# 3_7.net
KiCad netlist of a schematic drawn in Altium Designer
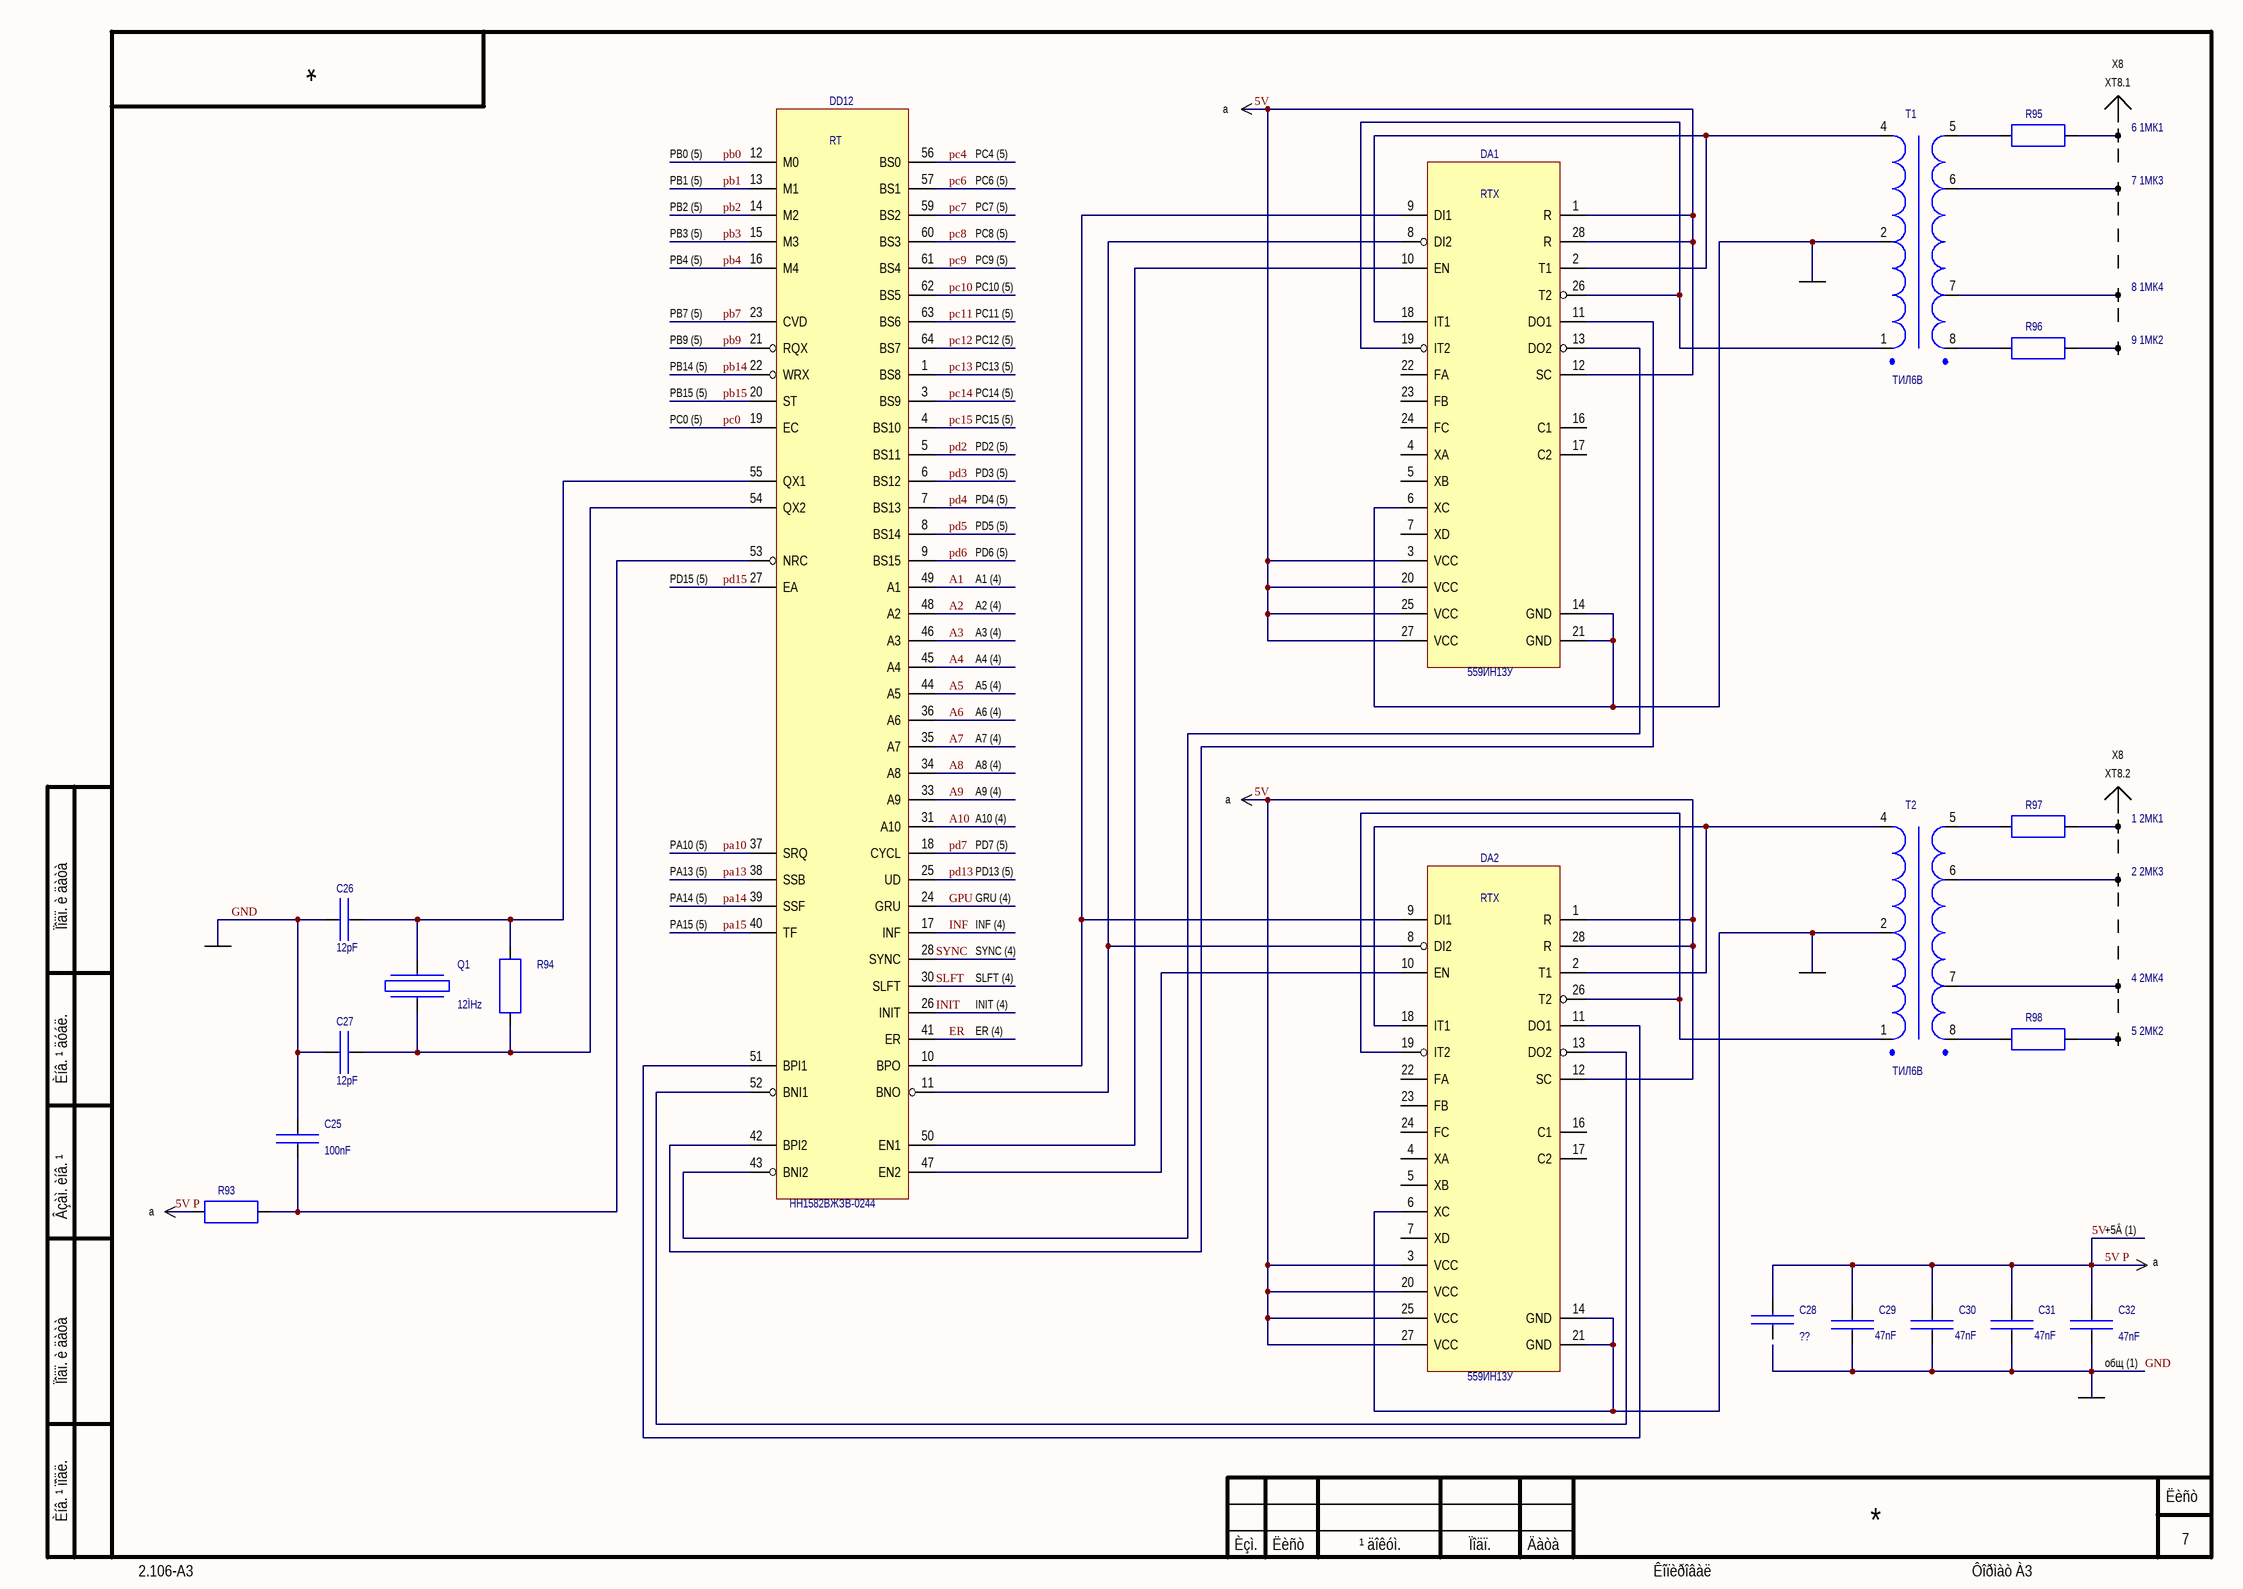
[diagram p0: Э3_7.SchDoc]

(export (version "E")
  (design (tool "Eeschema 10.0.6"))
  (components
    (comp (ref "C25") (value "100nF") (footprint "PcbLib1:CAP0805") (libsource (lib "Schlib1") (part "C_2")))
    (comp (ref "C26") (value "12pF") (footprint "PcbLib1:CAP0805") (libsource (lib "Schlib1") (part "C")))
    (comp (ref "C27") (value "12pF") (footprint "PcbLib1:CAP0805") (libsource (lib "Schlib1") (part "C")))
    (comp (ref "C28") (value "??") (footprint "PcbLib1:CAP0805") (libsource (lib "Schlib1") (part "C")))
    (comp (ref "C29") (value "47nF") (footprint "PcbLib1:CAP0805") (libsource (lib "Schlib1") (part "C")))
    (comp (ref "C30") (value "47nF") (footprint "PcbLib1:CAP0805") (libsource (lib "Schlib1") (part "C")))
    (comp (ref "C31") (value "47nF") (footprint "PcbLib1:CAP0805") (libsource (lib "Schlib1") (part "C")))
    (comp (ref "C32") (value "47nF") (footprint "PcbLib1:CAP0805") (libsource (lib "Schlib1") (part "C_2")))
    (comp (ref "DA1")
      (value "559ИН13У")
      (footprint "PcbLib1:H09.28-1B")
      (libsource (lib "Schlib1") (part "559ИН13У"))
    )
    (comp (ref "DA2")
      (value "559ИН13У")
      (footprint "PcbLib1:H09.28-1B")
      (libsource (lib "Schlib1") (part "559ИН13У"))
    )
    (comp (ref "DD12")
      (value "НН1582ВЖЗВ-0244")
      (footprint "PcbLib1:H18.64-1B")
      (libsource (lib "Schlib1") (part "НН1582ВЖЗВ-0244"))
    )
    (comp (ref "Q1") (value "12МHz") (libsource (lib "Schlib1") (part "Q_1")))
    (comp (ref "R93") (value "100k") (footprint "PcbLib1:RES0805") (libsource (lib "Schlib1") (part "R")))
    (comp (ref "R94") (value "240k") (footprint "PcbLib1:RES0805") (libsource (lib "Schlib1") (part "R")))
    (comp (ref "R95") (value "56") (footprint "PcbLib1:RES0805") (libsource (lib "Schlib1") (part "R")))
    (comp (ref "R96") (value "56") (footprint "PcbLib1:RES0805") (libsource (lib "Schlib1") (part "R_1")))
    (comp (ref "R97") (value "56") (footprint "PcbLib1:RES0805") (libsource (lib "Schlib1") (part "R")))
    (comp (ref "R98") (value "56") (footprint "PcbLib1:RES0805") (libsource (lib "Schlib1") (part "R")))
    (comp (ref "T1") (value "ТИЛ6B") (footprint "PcbLib1:TIL6V") (libsource (lib "Schlib1") (part "ТИЛ6B")))
    (comp (ref "T2") (value "ТИЛ6B") (footprint "PcbLib1:TIL6V") (libsource (lib "Schlib1") (part "ТИЛ6B")))
    (comp (ref "X8") (value "1 2МК1") (footprint "PcbLib1:PLD10") (libsource (lib "Schlib1") (part "PLD10")))
  )
  (nets
    (net (code "1") (name "/5V") (class "Default")
      (node (ref "C28") (pin "1") (pintype "passive"))
      (node (ref "C29") (pin "2") (pintype "passive"))
      (node (ref "C30") (pin "2") (pintype "passive"))
      (node (ref "C31") (pin "2") (pintype "passive"))
      (node (ref "C32") (pin "2") (pintype "passive"))
      (node (ref "DA1") (pin "1") (pinfunction "R_1") (pintype "passive"))
      (node (ref "DA1") (pin "12") (pinfunction "SC_12") (pintype "passive"))
      (node (ref "DA1") (pin "20") (pinfunction "VCC_20") (pintype "passive"))
      (node (ref "DA1") (pin "25") (pinfunction "VCC_25") (pintype "passive"))
      (node (ref "DA1") (pin "27") (pinfunction "VCC_27") (pintype "passive"))
      (node (ref "DA1") (pin "28") (pinfunction "R_28") (pintype "passive"))
      (node (ref "DA1") (pin "3") (pinfunction "VCC_3") (pintype "passive"))
      (node (ref "DA2") (pin "1") (pinfunction "R_1") (pintype "passive"))
      (node (ref "DA2") (pin "12") (pinfunction "SC_12") (pintype "passive"))
      (node (ref "DA2") (pin "20") (pinfunction "VCC_20") (pintype "passive"))
      (node (ref "DA2") (pin "25") (pinfunction "VCC_25") (pintype "passive"))
      (node (ref "DA2") (pin "27") (pinfunction "VCC_27") (pintype "passive"))
      (node (ref "DA2") (pin "28") (pinfunction "R_28") (pintype "passive"))
      (node (ref "DA2") (pin "3") (pinfunction "VCC_3") (pintype "passive"))
      (node (ref "R93") (pin "1") (pintype "passive"))
    )
    (net (code "2") (name "/A1") (class "Default")
      (node (ref "DD12") (pin "49") (pinfunction "A1_49") (pintype "passive"))
    )
    (net (code "3") (name "/A2") (class "Default")
      (node (ref "DD12") (pin "48") (pinfunction "A2_48") (pintype "passive"))
    )
    (net (code "4") (name "/A3") (class "Default")
      (node (ref "DD12") (pin "46") (pinfunction "A3_46") (pintype "passive"))
    )
    (net (code "5") (name "/A4") (class "Default")
      (node (ref "DD12") (pin "45") (pinfunction "A4_45") (pintype "passive"))
    )
    (net (code "6") (name "/A5") (class "Default")
      (node (ref "DD12") (pin "44") (pinfunction "A5_44") (pintype "passive"))
    )
    (net (code "7") (name "/A6") (class "Default")
      (node (ref "DD12") (pin "36") (pinfunction "A6_36") (pintype "passive"))
    )
    (net (code "8") (name "/A7") (class "Default")
      (node (ref "DD12") (pin "35") (pinfunction "A7_35") (pintype "passive"))
    )
    (net (code "9") (name "/A8") (class "Default")
      (node (ref "DD12") (pin "34") (pinfunction "A8_34") (pintype "passive"))
    )
    (net (code "10") (name "/A9") (class "Default")
      (node (ref "DD12") (pin "33") (pinfunction "A9_33") (pintype "passive"))
    )
    (net (code "11") (name "/A10") (class "Default")
      (node (ref "DD12") (pin "31") (pinfunction "A10_31") (pintype "passive"))
    )
    (net (code "12") (name "/ER") (class "Default")
      (node (ref "DD12") (pin "41") (pinfunction "ER_41") (pintype "passive"))
    )
    (net (code "13") (name "/GND") (class "Default")
      (node (ref "C25") (pin "2") (pintype "passive"))
      (node (ref "C26") (pin "1") (pintype "passive"))
      (node (ref "C27") (pin "1") (pintype "passive"))
      (node (ref "C29") (pin "1") (pintype "passive"))
      (node (ref "C30") (pin "1") (pintype "passive"))
      (node (ref "C31") (pin "1") (pintype "passive"))
      (node (ref "C32") (pin "1") (pintype "passive"))
      (node (ref "DA2") (pin "14") (pinfunction "GND_14") (pintype "passive"))
      (node (ref "DA2") (pin "21") (pinfunction "GND_21") (pintype "passive"))
      (node (ref "DA2") (pin "6") (pinfunction "XC_6") (pintype "passive"))
      (node (ref "T2") (pin "2") (pintype "passive"))
    )
    (net (code "14") (name "/GPU") (class "Default")
      (node (ref "DD12") (pin "24") (pinfunction "GRU_24") (pintype "passive"))
    )
    (net (code "15") (name "/INF") (class "Default")
      (node (ref "DD12") (pin "17") (pinfunction "INF_17") (pintype "passive"))
    )
    (net (code "16") (name "/INIT") (class "Default")
      (node (ref "DD12") (pin "26") (pinfunction "INIT_26") (pintype "passive"))
    )
    (net (code "17") (name "/SLFT") (class "Default")
      (node (ref "DD12") (pin "30") (pinfunction "SLFT_30") (pintype "passive"))
    )
    (net (code "18") (name "/SYNC") (class "Default")
      (node (ref "DD12") (pin "28") (pinfunction "SYNC_28") (pintype "passive"))
    )
    (net (code "19") (name "/pa10") (class "Default")
      (node (ref "DD12") (pin "37") (pinfunction "SRQ_37") (pintype "passive"))
    )
    (net (code "20") (name "/pa13") (class "Default")
      (node (ref "DD12") (pin "38") (pinfunction "SSB_38") (pintype "passive"))
    )
    (net (code "21") (name "/pa14") (class "Default")
      (node (ref "DD12") (pin "39") (pinfunction "SSF_39") (pintype "passive"))
    )
    (net (code "22") (name "/pa15") (class "Default")
      (node (ref "DD12") (pin "40") (pinfunction "TF_40") (pintype "passive"))
    )
    (net (code "23") (name "/pb0") (class "Default")
      (node (ref "DD12") (pin "12") (pinfunction "M0_12") (pintype "passive"))
    )
    (net (code "24") (name "/pb1") (class "Default")
      (node (ref "DD12") (pin "13") (pinfunction "M1_13") (pintype "passive"))
    )
    (net (code "25") (name "/pb2") (class "Default")
      (node (ref "DD12") (pin "14") (pinfunction "M2_14") (pintype "passive"))
    )
    (net (code "26") (name "/pb3") (class "Default")
      (node (ref "DD12") (pin "15") (pinfunction "M3_15") (pintype "passive"))
    )
    (net (code "27") (name "/pb4") (class "Default")
      (node (ref "DD12") (pin "16") (pinfunction "M4_16") (pintype "passive"))
    )
    (net (code "28") (name "/pb7") (class "Default")
      (node (ref "DD12") (pin "23") (pinfunction "CVD_23") (pintype "passive"))
    )
    (net (code "29") (name "/pb9") (class "Default")
      (node (ref "DD12") (pin "21") (pinfunction "RQX_21") (pintype "passive"))
    )
    (net (code "30") (name "/pb14") (class "Default")
      (node (ref "DD12") (pin "22") (pinfunction "WRX_22") (pintype "passive"))
    )
    (net (code "31") (name "/pb15") (class "Default")
      (node (ref "DD12") (pin "20") (pinfunction "ST_20") (pintype "passive"))
    )
    (net (code "32") (name "/pc0") (class "Default")
      (node (ref "DD12") (pin "19") (pinfunction "EC_19") (pintype "passive"))
    )
    (net (code "33") (name "/pc4") (class "Default")
      (node (ref "DD12") (pin "56") (pinfunction "BS0_56") (pintype "passive"))
    )
    (net (code "34") (name "/pc6") (class "Default")
      (node (ref "DD12") (pin "57") (pinfunction "BS1_57") (pintype "passive"))
    )
    (net (code "35") (name "/pc7") (class "Default")
      (node (ref "DD12") (pin "59") (pinfunction "BS2_59") (pintype "passive"))
    )
    (net (code "36") (name "/pc8") (class "Default")
      (node (ref "DD12") (pin "60") (pinfunction "BS3_60") (pintype "passive"))
    )
    (net (code "37") (name "/pc9") (class "Default")
      (node (ref "DD12") (pin "61") (pinfunction "BS4_61") (pintype "passive"))
    )
    (net (code "38") (name "/pc10") (class "Default")
      (node (ref "DD12") (pin "62") (pinfunction "BS5_62") (pintype "passive"))
    )
    (net (code "39") (name "/pc11") (class "Default")
      (node (ref "DD12") (pin "63") (pinfunction "BS6_63") (pintype "passive"))
    )
    (net (code "40") (name "/pc12") (class "Default")
      (node (ref "DD12") (pin "64") (pinfunction "BS7_64") (pintype "passive"))
    )
    (net (code "41") (name "/pc13") (class "Default")
      (node (ref "DD12") (pin "1") (pinfunction "BS8_1") (pintype "passive"))
    )
    (net (code "42") (name "/pc14") (class "Default")
      (node (ref "DD12") (pin "3") (pinfunction "BS9_3") (pintype "passive"))
    )
    (net (code "43") (name "/pc15") (class "Default")
      (node (ref "DD12") (pin "4") (pinfunction "BS10_4") (pintype "passive"))
    )
    (net (code "44") (name "/pd2") (class "Default")
      (node (ref "DD12") (pin "5") (pinfunction "BS11_5") (pintype "passive"))
    )
    (net (code "45") (name "/pd3") (class "Default")
      (node (ref "DD12") (pin "6") (pinfunction "BS12_6") (pintype "passive"))
    )
    (net (code "46") (name "/pd4") (class "Default")
      (node (ref "DD12") (pin "7") (pinfunction "BS13_7") (pintype "passive"))
    )
    (net (code "47") (name "/pd5") (class "Default")
      (node (ref "DD12") (pin "8") (pinfunction "BS14_8") (pintype "passive"))
    )
    (net (code "48") (name "/pd6") (class "Default")
      (node (ref "DD12") (pin "9") (pinfunction "BS15_9") (pintype "passive"))
    )
    (net (code "49") (name "/pd7") (class "Default")
      (node (ref "DD12") (pin "18") (pinfunction "CYCL_18") (pintype "passive"))
    )
    (net (code "50") (name "/pd13") (class "Default")
      (node (ref "DD12") (pin "25") (pinfunction "UD_25") (pintype "passive"))
    )
    (net (code "51") (name "/pd15") (class "Default")
      (node (ref "DD12") (pin "27") (pinfunction "EA_27") (pintype "passive"))
    )
    (net (code "52") (name "Net-(DA1-DI1)") (class "Default")
      (node (ref "DA1") (pin "9") (pinfunction "DI1_9") (pintype "passive"))
      (node (ref "DA2") (pin "9") (pinfunction "DI1_9") (pintype "passive"))
      (node (ref "DD12") (pin "10") (pinfunction "BPO_10") (pintype "passive"))
    )
    (net (code "53") (name "Net-(DA1-DI2)") (class "Default")
      (node (ref "DA1") (pin "8") (pinfunction "DI2_8") (pintype "passive"))
      (node (ref "DA2") (pin "8") (pinfunction "DI2_8") (pintype "passive"))
      (node (ref "DD12") (pin "11") (pinfunction "BNO_11") (pintype "passive"))
    )
    (net (code "54") (name "Net-(DA1-DO1)") (class "Default")
      (node (ref "DA1") (pin "11") (pinfunction "DO1_11") (pintype "passive"))
      (node (ref "DD12") (pin "42") (pinfunction "BPI2_42") (pintype "passive"))
    )
    (net (code "55") (name "Net-(DA1-DO2)") (class "Default")
      (node (ref "DA1") (pin "13") (pinfunction "DO2_13") (pintype "passive"))
      (node (ref "DD12") (pin "43") (pinfunction "BNI2_43") (pintype "passive"))
    )
    (net (code "56") (name "Net-(DA1-EN)") (class "Default")
      (node (ref "DA1") (pin "10") (pinfunction "EN_10") (pintype "passive"))
      (node (ref "DD12") (pin "50") (pinfunction "EN1_50") (pintype "passive"))
    )
    (net (code "57") (name "Net-(DA1-IT1)") (class "Default")
      (node (ref "DA1") (pin "18") (pinfunction "IT1_18") (pintype "passive"))
      (node (ref "DA1") (pin "2") (pinfunction "T1_2") (pintype "passive"))
      (node (ref "T1") (pin "4") (pintype "passive"))
    )
    (net (code "58") (name "Net-(DA1-IT2)") (class "Default")
      (node (ref "DA1") (pin "19") (pinfunction "IT2_19") (pintype "passive"))
      (node (ref "DA1") (pin "26") (pinfunction "T2_26") (pintype "passive"))
      (node (ref "T1") (pin "1") (pintype "passive"))
    )
    (net (code "59") (name "Net-(DA1-XC)") (class "Default")
      (node (ref "DA1") (pin "14") (pinfunction "GND_14") (pintype "passive"))
      (node (ref "DA1") (pin "21") (pinfunction "GND_21") (pintype "passive"))
      (node (ref "DA1") (pin "6") (pinfunction "XC_6") (pintype "passive"))
      (node (ref "T1") (pin "2") (pintype "passive"))
    )
    (net (code "60") (name "Net-(DA2-DO1)") (class "Default")
      (node (ref "DA2") (pin "11") (pinfunction "DO1_11") (pintype "passive"))
      (node (ref "DD12") (pin "51") (pinfunction "BPI1_51") (pintype "passive"))
    )
    (net (code "61") (name "Net-(DA2-DO2)") (class "Default")
      (node (ref "DA2") (pin "13") (pinfunction "DO2_13") (pintype "passive"))
      (node (ref "DD12") (pin "52") (pinfunction "BNI1_52") (pintype "passive"))
    )
    (net (code "62") (name "Net-(DA2-EN)") (class "Default")
      (node (ref "DA2") (pin "10") (pinfunction "EN_10") (pintype "passive"))
      (node (ref "DD12") (pin "47") (pinfunction "EN2_47") (pintype "passive"))
    )
    (net (code "63") (name "Net-(DA2-IT1)") (class "Default")
      (node (ref "DA2") (pin "18") (pinfunction "IT1_18") (pintype "passive"))
      (node (ref "DA2") (pin "2") (pinfunction "T1_2") (pintype "passive"))
      (node (ref "T2") (pin "4") (pintype "passive"))
    )
    (net (code "64") (name "Net-(DA2-IT2)") (class "Default")
      (node (ref "DA2") (pin "19") (pinfunction "IT2_19") (pintype "passive"))
      (node (ref "DA2") (pin "26") (pinfunction "T2_26") (pintype "passive"))
      (node (ref "T2") (pin "1") (pintype "passive"))
    )
    (net (code "65") (name "Net-(DD12-NRC)") (class "Default")
      (node (ref "C25") (pin "1") (pintype "passive"))
      (node (ref "DD12") (pin "53") (pinfunction "NRC_53") (pintype "passive"))
      (node (ref "R93") (pin "2") (pintype "passive"))
    )
    (net (code "66") (name "Net-(DD12-QX1)") (class "Default")
      (node (ref "C26") (pin "2") (pintype "passive"))
      (node (ref "DD12") (pin "55") (pinfunction "QX1_55") (pintype "passive"))
      (node (ref "Q1") (pin "2") (pintype "passive"))
      (node (ref "R94") (pin "2") (pintype "passive"))
    )
    (net (code "67") (name "Net-(DD12-QX2)") (class "Default")
      (node (ref "C27") (pin "2") (pintype "passive"))
      (node (ref "DD12") (pin "54") (pinfunction "QX2_54") (pintype "passive"))
      (node (ref "Q1") (pin "1") (pintype "passive"))
      (node (ref "R94") (pin "1") (pintype "passive"))
    )
    (net (code "68") (name "Net-(R95-Pad1)") (class "Default")
      (node (ref "R95") (pin "1") (pintype "passive"))
      (node (ref "T1") (pin "5") (pintype "passive"))
    )
    (net (code "69") (name "Net-(R96-Pad1)") (class "Default")
      (node (ref "R96") (pin "1") (pintype "passive"))
      (node (ref "T1") (pin "8") (pintype "passive"))
    )
    (net (code "70") (name "Net-(R97-Pad1)") (class "Default")
      (node (ref "R97") (pin "1") (pintype "passive"))
      (node (ref "T2") (pin "5") (pintype "passive"))
    )
    (net (code "71") (name "Net-(R97-Pad2)") (class "Default")
      (node (ref "R97") (pin "2") (pintype "passive"))
      (node (ref "X8") (pin "1") (pinfunction "1_1") (pintype "passive"))
    )
    (net (code "72") (name "Net-(R98-Pad1)") (class "Default")
      (node (ref "R98") (pin "1") (pintype "passive"))
      (node (ref "T2") (pin "8") (pintype "passive"))
    )
    (net (code "73") (name "Net-(X8B-1)") (class "Default")
      (node (ref "T2") (pin "6") (pintype "passive"))
      (node (ref "X8") (pin "2") (pinfunction "1_2") (pintype "passive"))
    )
    (net (code "74") (name "Net-(X8D-1)") (class "Default")
      (node (ref "T2") (pin "7") (pintype "passive"))
      (node (ref "X8") (pin "4") (pinfunction "1_4") (pintype "passive"))
    )
    (net (code "75") (name "Net-(X8E-1)") (class "Default")
      (node (ref "R98") (pin "2") (pintype "passive"))
      (node (ref "X8") (pin "5") (pinfunction "1_5") (pintype "passive"))
    )
    (net (code "76") (name "Net-(X8F-1)") (class "Default")
      (node (ref "R95") (pin "2") (pintype "passive"))
      (node (ref "X8") (pin "6") (pinfunction "1_6") (pintype "passive"))
    )
    (net (code "77") (name "Net-(X8G-1)") (class "Default")
      (node (ref "T1") (pin "6") (pintype "passive"))
      (node (ref "X8") (pin "7") (pinfunction "1_7") (pintype "passive"))
    )
    (net (code "78") (name "Net-(X8H-1)") (class "Default")
      (node (ref "T1") (pin "7") (pintype "passive"))
      (node (ref "X8") (pin "8") (pinfunction "1_8") (pintype "passive"))
    )
    (net (code "79") (name "Net-(X8I-1)") (class "Default")
      (node (ref "R96") (pin "2") (pintype "passive"))
      (node (ref "X8") (pin "9") (pinfunction "1_9") (pintype "passive"))
    )
    (net (code "80") (name "unconnected-(C28-Pad2)") (class "Default")
      (node (ref "C28") (pin "2") (pintype "passive"))
    )
    (net (code "81") (name "unconnected-(DA1-C1-Pad16)") (class "Default")
      (node (ref "DA1") (pin "16") (pinfunction "C1_16") (pintype "passive"))
    )
    (net (code "82") (name "unconnected-(DA1-C2-Pad17)") (class "Default")
      (node (ref "DA1") (pin "17") (pinfunction "C2_17") (pintype "passive"))
    )
    (net (code "83") (name "unconnected-(DA1-FA-Pad22)") (class "Default")
      (node (ref "DA1") (pin "22") (pinfunction "FA_22") (pintype "passive"))
    )
    (net (code "84") (name "unconnected-(DA1-FB-Pad23)") (class "Default")
      (node (ref "DA1") (pin "23") (pinfunction "FB_23") (pintype "passive"))
    )
    (net (code "85") (name "unconnected-(DA1-FC-Pad24)") (class "Default")
      (node (ref "DA1") (pin "24") (pinfunction "FC_24") (pintype "passive"))
    )
    (net (code "86") (name "unconnected-(DA1-XA-Pad4)") (class "Default")
      (node (ref "DA1") (pin "4") (pinfunction "XA_4") (pintype "passive"))
    )
    (net (code "87") (name "unconnected-(DA1-XB-Pad5)") (class "Default")
      (node (ref "DA1") (pin "5") (pinfunction "XB_5") (pintype "passive"))
    )
    (net (code "88") (name "unconnected-(DA1-XD-Pad7)") (class "Default")
      (node (ref "DA1") (pin "7") (pinfunction "XD_7") (pintype "passive"))
    )
    (net (code "89") (name "unconnected-(DA2-C1-Pad16)") (class "Default")
      (node (ref "DA2") (pin "16") (pinfunction "C1_16") (pintype "passive"))
    )
    (net (code "90") (name "unconnected-(DA2-C2-Pad17)") (class "Default")
      (node (ref "DA2") (pin "17") (pinfunction "C2_17") (pintype "passive"))
    )
    (net (code "91") (name "unconnected-(DA2-FA-Pad22)") (class "Default")
      (node (ref "DA2") (pin "22") (pinfunction "FA_22") (pintype "passive"))
    )
    (net (code "92") (name "unconnected-(DA2-FB-Pad23)") (class "Default")
      (node (ref "DA2") (pin "23") (pinfunction "FB_23") (pintype "passive"))
    )
    (net (code "93") (name "unconnected-(DA2-FC-Pad24)") (class "Default")
      (node (ref "DA2") (pin "24") (pinfunction "FC_24") (pintype "passive"))
    )
    (net (code "94") (name "unconnected-(DA2-XA-Pad4)") (class "Default")
      (node (ref "DA2") (pin "4") (pinfunction "XA_4") (pintype "passive"))
    )
    (net (code "95") (name "unconnected-(DA2-XB-Pad5)") (class "Default")
      (node (ref "DA2") (pin "5") (pinfunction "XB_5") (pintype "passive"))
    )
    (net (code "96") (name "unconnected-(DA2-XD-Pad7)") (class "Default")
      (node (ref "DA2") (pin "7") (pinfunction "XD_7") (pintype "passive"))
    )
  )
)
